# CON2.net
KiCad netlist of a schematic drawn in Altium Designer
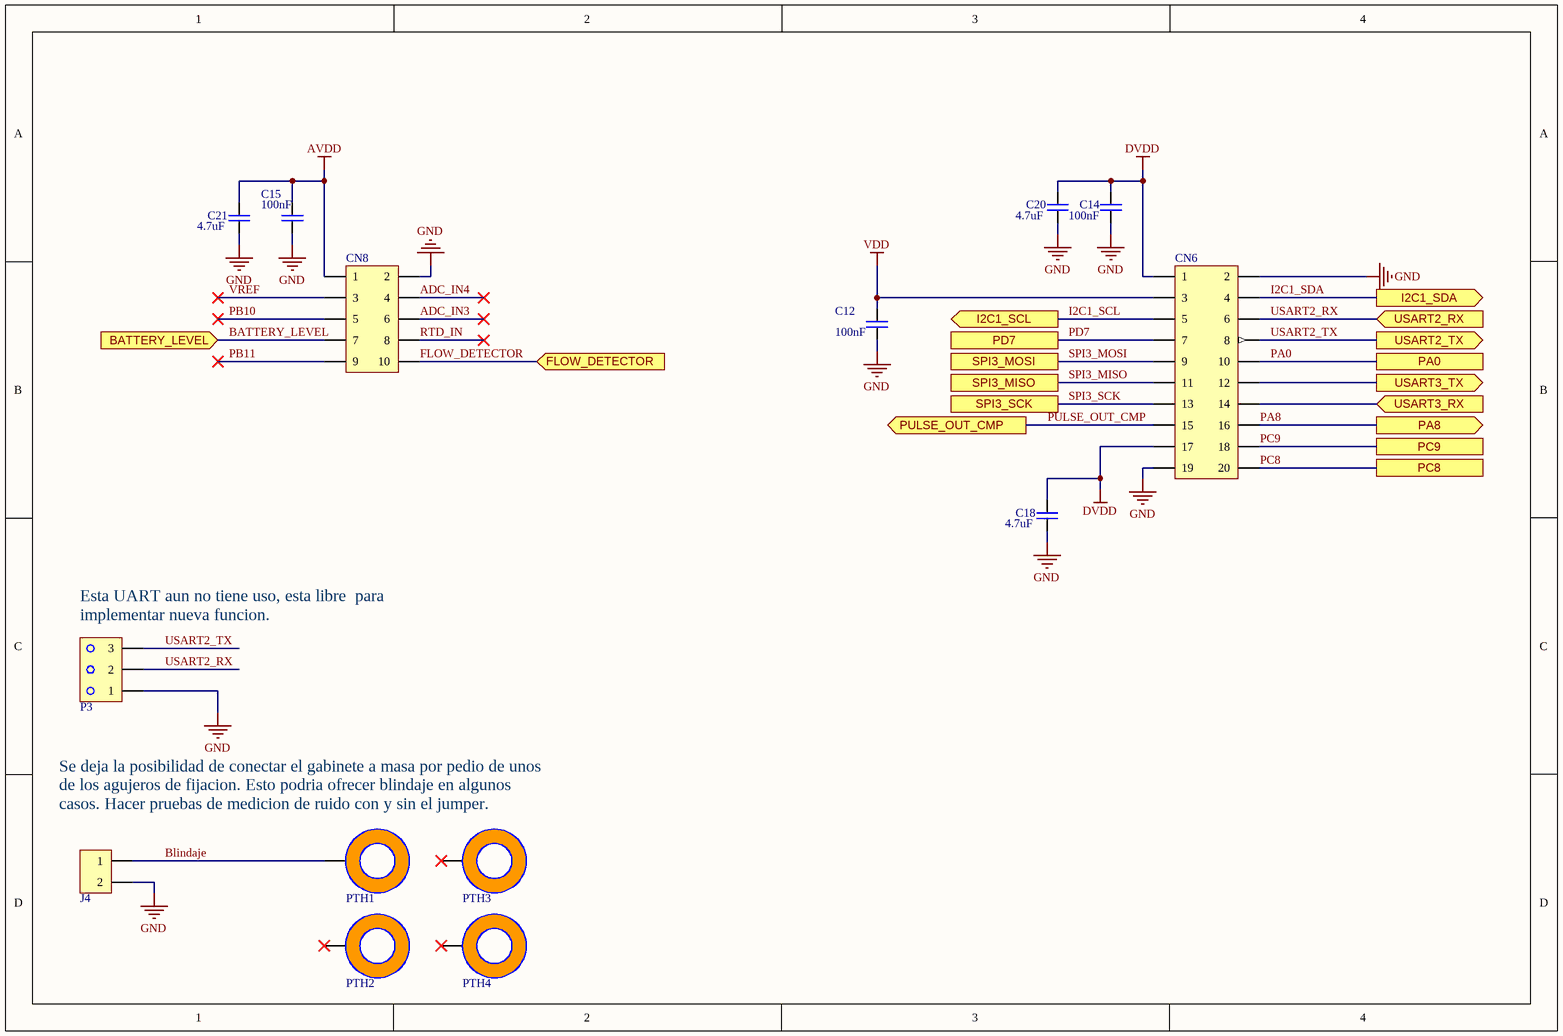
[diagram p0: CON2.SchDoc]

(export (version "E")
  (design (tool "Eeschema 10.0.6"))
  (components
    (comp (ref "C12")
      (value "100nF")
      (footprint "CAP_SM0805_YAGEOCC2_N")
      (description "CAP 100nF SM0805 X7R 25V YAGEO CC2")
      (fields
        (field (name "MANUFACTURER") "Yageo")
        (field (name "MANUFACTURER PART NUMBER") "CC0805KRX7R8BB104")
      )
      (libsource (lib "Yageo") (part "CC0805KRX7R8BB104"))
    )
    (comp (ref "C14")
      (value "100nF")
      (footprint "CAP_SM0805_YAGEOCC2_N")
      (description "CAP 100nF SM0805 X7R 25V YAGEO CC2")
      (fields
        (field (name "MANUFACTURER") "Yageo")
        (field (name "MANUFACTURER PART NUMBER") "CC0805KRX7R8BB104")
      )
      (libsource (lib "Yageo") (part "CC0805KRX7R8BB104"))
    )
    (comp (ref "C15")
      (value "100nF")
      (footprint "CAP_SM0805_YAGEOCC2_N")
      (description "CAP 100nF SM0805 X7R 25V YAGEO CC2")
      (fields
        (field (name "MANUFACTURER") "Yageo")
        (field (name "MANUFACTURER PART NUMBER") "CC0805KRX7R8BB104")
      )
      (libsource (lib "Yageo") (part "CC0805KRX7R8BB104"))
    )
    (comp (ref "C18")
      (value "4.7uF")
      (footprint "CAP_SM0805_YAGEOCC2_N")
      (description "CAP 4.7uF SM0805 X5R 10V YAGEO CC2")
      (fields
        (field (name "MANUFACTURER") "Yageo")
        (field (name "MANUFACTURER PART NUMBER") "CC0805KRX5R6BB475")
      )
      (libsource (lib "Yageo") (part "CC0805KRX5R6BB475"))
    )
    (comp (ref "C20")
      (value "4.7uF")
      (footprint "CAP_SM0805_YAGEOCC2_N")
      (description "CAP 4.7uF SM0805 X5R 10V YAGEO CC2")
      (fields
        (field (name "MANUFACTURER") "Yageo")
        (field (name "MANUFACTURER PART NUMBER") "CC0805KRX5R6BB475")
      )
      (libsource (lib "Yageo") (part "CC0805KRX5R6BB475"))
    )
    (comp (ref "C21")
      (value "4.7uF")
      (footprint "CAP_SM0805_YAGEOCC2_N")
      (description "CAP 4.7uF SM0805 X5R 10V YAGEO CC2")
      (fields
        (field (name "MANUFACTURER") "Yageo")
        (field (name "MANUFACTURER PART NUMBER") "CC0805KRX5R6BB475")
      )
      (libsource (lib "Yageo") (part "CC0805KRX5R6BB475"))
    )
    (comp (ref "CN6")
      (value "DZ254R-22-20-63")
      (footprint "HEADER PIN 2X10")
      (description "2 x 10 - true hole 2.54mm")
      (fields (field (name "MANUFACTURER") "DEALON"))
      (libsource (lib "header_pin") (part "DZ254R-22-20-63"))
    )
    (comp (ref "CN8")
      (value "Uar Equivalente")
      (footprint "HEADER PIN 2X5 MIRROR")
      (description "2 x 5 - true hole 2.54mm")
      (fields
        (field (name "MANUFACTURER") "DEALON")
        (field (name "MANUFACTURER PART NUMBER") "DZ254R-22-10-63")
      )
      (libsource (lib "header_pin") (part "DZ254R-22-10-63"))
    )
    (comp (ref "J4")
      (value "Usar Equivalente")
      (footprint "HEADER PIN 1X2")
      (description "1 x 2 - true hole  2.54mm - Pb free")
      (fields
        (field (name "MANUFACTURER") "Amphenol ICC")
        (field (name "MANUFACTURER PART NUMBER") "54101-T0602LF")
      )
      (libsource (lib "header_pin") (part "54101-T0602LF"))
    )
    (comp (ref "P3")
      (value "WJ15EDGVC-3.81-3P")
      (footprint "HEADER PLUG 3")
      (description "TERM BLOK FEMALE 1X3 3.81MM")
      (fields (field (name "MANUFACTURER") "Ningbo Kangnex Elec"))
      (libsource (lib "plug") (part "WJ15EDGVC-3.81-3P"))
    )
    (comp (ref "PTH1")
      (value "PTH-3MM-M")
      (footprint "PTH_M3_M")
      (description "Agujero de montaje metalizado roscas M3. Drill de tamaño medio.")
      (libsource (lib "montaje") (part "PTH-3MM-M"))
    )
    (comp (ref "PTH2")
      (value "PTH-3MM-M")
      (footprint "PTH_M3_M")
      (description "Agujero de montaje metalizado roscas M3. Drill de tamaño medio.")
      (libsource (lib "montaje") (part "PTH-3MM-M"))
    )
    (comp (ref "PTH3")
      (value "PTH-3MM-M")
      (footprint "PTH_M3_M")
      (description "Agujero de montaje metalizado roscas M3. Drill de tamaño medio.")
      (libsource (lib "montaje") (part "PTH-3MM-M"))
    )
    (comp (ref "PTH4")
      (value "PTH-3MM-M")
      (footprint "PTH_M3_M")
      (description "Agujero de montaje metalizado roscas M3. Drill de tamaño medio.")
      (libsource (lib "montaje") (part "PTH-3MM-M"))
    )
  )
  (nets
    (net (code "1") (name "/ADC_IN3") (class "Default")
      (node (ref "CN8") (pin "6") (pinfunction "6_6") (pintype "passive+no_connect"))
    )
    (net (code "2") (name "/ADC_IN4") (class "Default")
      (node (ref "CN8") (pin "4") (pinfunction "4_4") (pintype "passive+no_connect"))
    )
    (net (code "3") (name "/BATTERY_LEVEL") (class "Default")
      (node (ref "CN8") (pin "7") (pinfunction "7_7") (pintype "passive"))
    )
    (net (code "4") (name "/Blindaje") (class "Default")
      (node (ref "J4") (pin "1") (pinfunction "1_1") (pintype "passive"))
      (node (ref "PTH1") (pin "1") (pinfunction "1_1") (pintype "passive"))
    )
    (net (code "5") (name "/FLOW_DETECTOR") (class "Default")
      (node (ref "CN8") (pin "10") (pinfunction "10_10") (pintype "passive"))
    )
    (net (code "6") (name "/I2C1_SCL") (class "Default")
      (node (ref "CN6") (pin "5") (pinfunction "5_5") (pintype "passive"))
    )
    (net (code "7") (name "/I2C1_SDA") (class "Default")
      (node (ref "CN6") (pin "4") (pinfunction "4_4") (pintype "passive"))
    )
    (net (code "8") (name "/PA0") (class "Default")
      (node (ref "CN6") (pin "10") (pinfunction "10_10") (pintype "passive"))
    )
    (net (code "9") (name "/PA8") (class "Default")
      (node (ref "CN6") (pin "16") (pinfunction "16_16") (pintype "passive"))
    )
    (net (code "10") (name "/PB10") (class "Default")
      (node (ref "CN8") (pin "5") (pinfunction "5_5") (pintype "passive+no_connect"))
    )
    (net (code "11") (name "/PB11") (class "Default")
      (node (ref "CN8") (pin "9") (pinfunction "9_9") (pintype "passive+no_connect"))
    )
    (net (code "12") (name "/PC8") (class "Default")
      (node (ref "CN6") (pin "20") (pinfunction "20_20") (pintype "passive"))
    )
    (net (code "13") (name "/PC9") (class "Default")
      (node (ref "CN6") (pin "18") (pinfunction "18_18") (pintype "passive"))
    )
    (net (code "14") (name "/PD7") (class "Default")
      (node (ref "CN6") (pin "7") (pinfunction "7_7") (pintype "passive"))
    )
    (net (code "15") (name "/PULSE_OUT_CMP") (class "Default")
      (node (ref "CN6") (pin "15") (pinfunction "15_15") (pintype "passive"))
    )
    (net (code "16") (name "/RTD_IN") (class "Default")
      (node (ref "CN8") (pin "8") (pinfunction "8_8") (pintype "passive+no_connect"))
    )
    (net (code "17") (name "/SPI3_MISO") (class "Default")
      (node (ref "CN6") (pin "11") (pinfunction "11_11") (pintype "passive"))
    )
    (net (code "18") (name "/SPI3_MOSI") (class "Default")
      (node (ref "CN6") (pin "9") (pinfunction "9_9") (pintype "passive"))
    )
    (net (code "19") (name "/SPI3_SCK") (class "Default")
      (node (ref "CN6") (pin "13") (pinfunction "13_13") (pintype "passive"))
    )
    (net (code "20") (name "/USART2_RX") (class "Default")
      (node (ref "CN6") (pin "6") (pinfunction "6_6") (pintype "passive"))
      (node (ref "P3") (pin "2") (pinfunction "2_2") (pintype "passive"))
    )
    (net (code "21") (name "/USART2_TX") (class "Default")
      (node (ref "CN6") (pin "8") (pinfunction "8_8") (pintype "output"))
      (node (ref "P3") (pin "3") (pinfunction "3_3") (pintype "passive"))
    )
    (net (code "22") (name "/USART3_RX") (class "Default")
      (node (ref "CN6") (pin "14") (pinfunction "14_14") (pintype "passive"))
    )
    (net (code "23") (name "/USART3_TX") (class "Default")
      (node (ref "CN6") (pin "12") (pinfunction "12_12") (pintype "passive"))
    )
    (net (code "24") (name "/VREF") (class "Default")
      (node (ref "CN8") (pin "3") (pinfunction "3_3") (pintype "passive+no_connect"))
    )
    (net (code "25") (name "AVDD") (class "Default")
      (node (ref "C15") (pin "1") (pintype "passive"))
      (node (ref "C21") (pin "1") (pintype "passive"))
      (node (ref "CN8") (pin "1") (pinfunction "1_1") (pintype "passive"))
    )
    (net (code "26") (name "DVDD") (class "Default")
      (node (ref "C14") (pin "1") (pintype "passive"))
      (node (ref "C18") (pin "1") (pintype "passive"))
      (node (ref "C20") (pin "1") (pintype "passive"))
      (node (ref "CN6") (pin "1") (pinfunction "1_1") (pintype "passive"))
      (node (ref "CN6") (pin "17") (pinfunction "17_17") (pintype "passive"))
    )
    (net (code "27") (name "GND") (class "Default")
      (node (ref "C12") (pin "2") (pintype "passive"))
      (node (ref "C14") (pin "2") (pintype "passive"))
      (node (ref "C15") (pin "2") (pintype "passive"))
      (node (ref "C18") (pin "2") (pintype "passive"))
      (node (ref "C20") (pin "2") (pintype "passive"))
      (node (ref "C21") (pin "2") (pintype "passive"))
      (node (ref "CN6") (pin "19") (pinfunction "19_19") (pintype "passive"))
      (node (ref "CN6") (pin "2") (pinfunction "2_2") (pintype "passive"))
      (node (ref "CN8") (pin "2") (pinfunction "2_2") (pintype "passive"))
      (node (ref "J4") (pin "2") (pinfunction "2_2") (pintype "passive"))
      (node (ref "P3") (pin "1") (pinfunction "1_1") (pintype "passive"))
    )
    (net (code "28") (name "VDD") (class "Default")
      (node (ref "C12") (pin "1") (pintype "passive"))
      (node (ref "CN6") (pin "3") (pinfunction "3_3") (pintype "passive"))
    )
    (net (code "29") (name "unconnected-(PTH2-Pad1)") (class "Default")
      (node (ref "PTH2") (pin "1") (pinfunction "1_1") (pintype "passive+no_connect"))
    )
    (net (code "30") (name "unconnected-(PTH3-Pad1)") (class "Default")
      (node (ref "PTH3") (pin "1") (pinfunction "1_1") (pintype "passive+no_connect"))
    )
    (net (code "31") (name "unconnected-(PTH4-Pad1)") (class "Default")
      (node (ref "PTH4") (pin "1") (pinfunction "1_1") (pintype "passive+no_connect"))
    )
  )
)
